# Scheme.net
KiCad netlist of a schematic drawn in Altium Designer
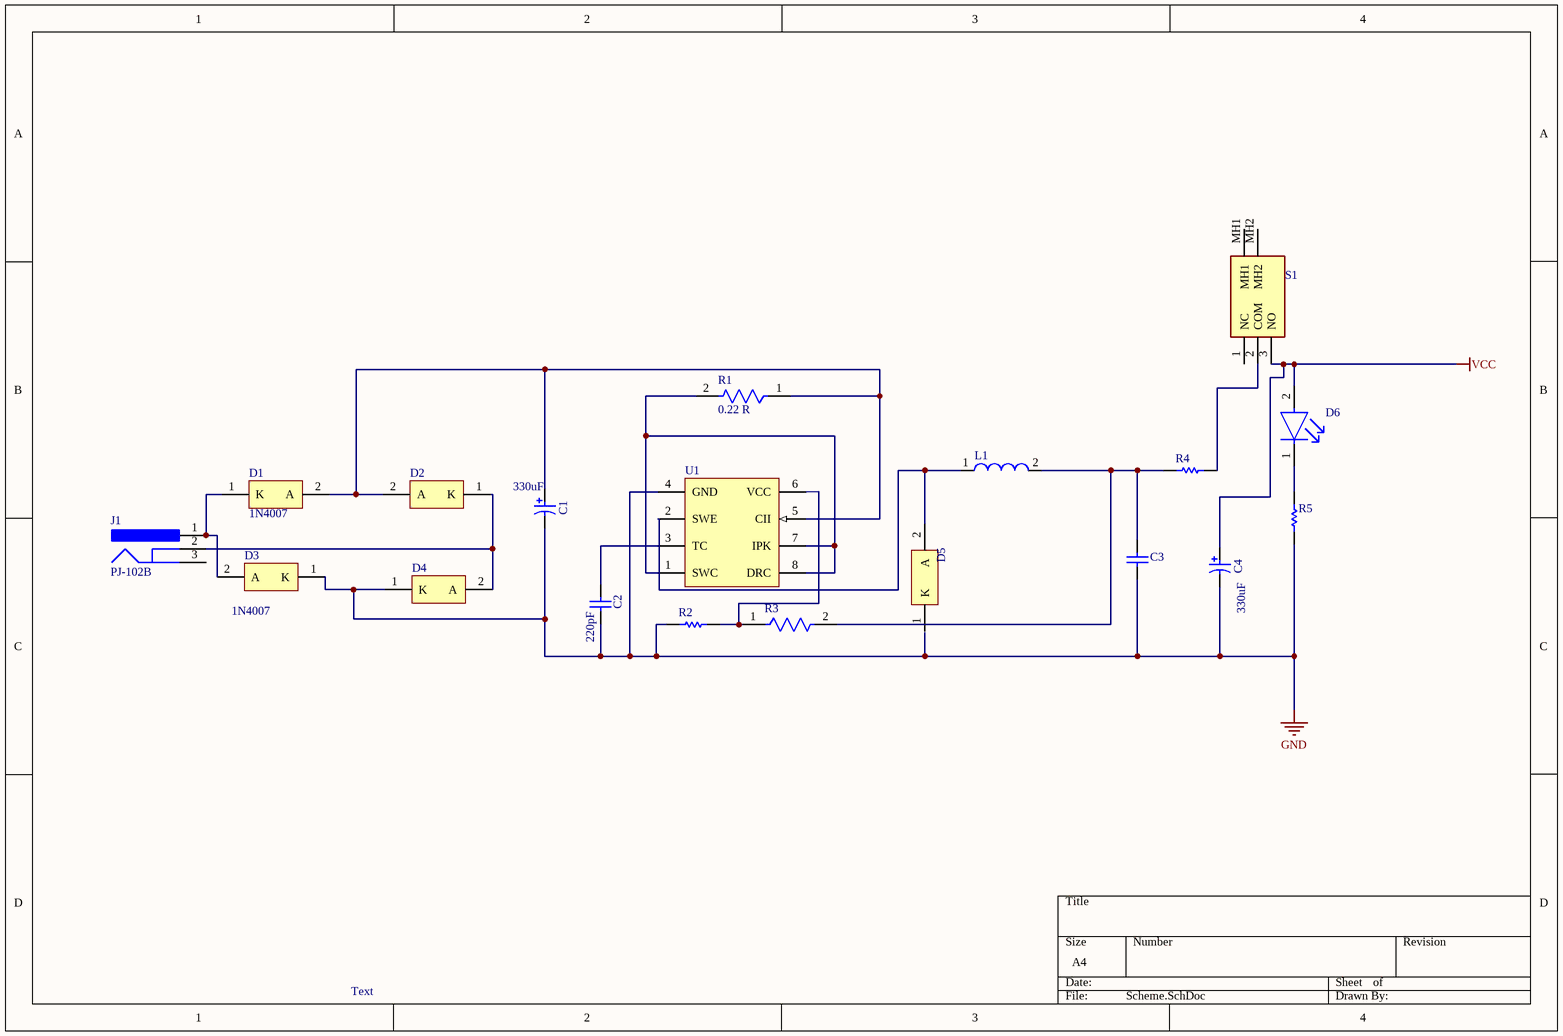
[diagram p0: Scheme.SchDoc]

(export (version "E")
  (design (tool "Eeschema 10.0.6"))
  (components
    (comp (ref "C1")
      (value "EEE-FK1V331P")
      (footprint "PNSC-EEE-FK1V331P_L")
      (description "Aluminum Electrolytic Capacitor, 330 uF, 35 V, -55 to 105 degC, 2-Pin CAPAE, RoHS, Tape and Reel")
      (fields (field (name "MANUFACTURER") "Panasonic"))
      (libsource (lib "Altium Content Vault") (part "CAP-P-2"))
    )
    (comp (ref "C2")
      (value "VJ0603D201KXAAJ")
      (footprint "CAPC1608X92X38LL15T08")
      (fields (field (name "MANUFACTURER") "Vitramon"))
      (libsource (lib "Altium Content Vault") (part "CAP"))
    )
    (comp (ref "C3")
      (value "GRM188R60J106ME47D")
      (footprint "CAPC1608X90X35NL10T15")
      (fields (field (name "MANUFACTURER") "Murata"))
      (libsource (lib "Altium Content Vault") (part "CAP"))
    )
    (comp (ref "C4")
      (value "EEE-FK1V331P")
      (footprint "PNSC-EEE-FK1V331P_L")
      (description "Aluminum Electrolytic Capacitor, 330 uF, 35 V, -55 to 105 degC, 2-Pin CAPAE, RoHS, Tape and Reel")
      (fields (field (name "MANUFACTURER") "Panasonic"))
      (libsource (lib "Altium Content Vault") (part "CAP-P-2"))
    )
    (comp (ref "D1")
      (value "1N4007")
      (footprint "ONSC-AXIAL_LEAD-2-59-10_P")
      (description "Standard Recovery Rectifier, 2-Pin Axial_Lead, Pb-Free, Bulk Bag")
      (fields (field (name "MANUFACTURER") "On Semiconductor"))
      (libsource (lib "") (part "ONSC-D-K1A2-2_A_1"))
    )
    (comp (ref "D2")
      (value "1N4007")
      (footprint "ONSC-AXIAL_LEAD-2-59-10_P")
      (description "Standard Recovery Rectifier, 2-Pin Axial_Lead, Pb-Free, Bulk Bag")
      (fields (field (name "MANUFACTURER") "On Semiconductor"))
      (libsource (lib "") (part "ONSC-D-K1A2-2_A_2"))
    )
    (comp (ref "D3")
      (value "1N4007")
      (footprint "ONSC-AXIAL_LEAD-2-59-10_P")
      (description "Standard Recovery Rectifier, 2-Pin Axial_Lead, Pb-Free, Bulk Bag")
      (fields (field (name "MANUFACTURER") "On Semiconductor"))
      (libsource (lib "") (part "ONSC-D-K1A2-2_A_2"))
    )
    (comp (ref "D4")
      (value "1N4007")
      (footprint "ONSC-AXIAL_LEAD-2-59-10_P")
      (description "Standard Recovery Rectifier, 2-Pin Axial_Lead, Pb-Free, Bulk Bag")
      (fields (field (name "MANUFACTURER") "On Semiconductor"))
      (libsource (lib "") (part "ONSC-D-K1A2-2_A_1"))
    )
    (comp (ref "D5")
      (value "MBRS140T3G")
      (footprint "ONSC-SMB-2-403A-03_H_V")
      (description "Schottky Power Rectifier, 2-Pin SMB, Pb-Free, Tape and Reel")
      (fields (field (name "MANUFACTURER") "On Semiconductor"))
      (libsource (lib "Altium Content Vault") (part "ONSC-D-K1A2-2_A"))
    )
    (comp (ref "D6")
      (value "LTST-C190GKT")
      (footprint "FP-LTST-C190GKT-MFG")
      (description "LED GREEN CLEAR CHIP SMD")
      (fields (field (name "VOLTAGE") "2V"))
      (libsource (lib "Altium Content Vault") (part "8706943c75ba83719d021d2fdc84c58"))
    )
    (comp (ref "J1")
      (value "PJ-102B")
      (footprint "CUI-PJ-102B_V")
      (fields (field (name "MANUFACTURER") "CUIInc."))
      (libsource (lib "Altium Content Vault") (part "JACK-2CD3-RN"))
    )
    (comp (ref "L1")
      (value "744774222")
      (footprint "WE-PD2-M")
      (description "SMD Power Inductor WE-PD2, L = 220 µH")
      (libsource (lib "Altium Content Vault") (part "PAS-IND-INDUCTOR-2"))
    )
    (comp (ref "R1")
      (value "CRCW04022K70FKED")
      (footprint "FP-CRCW0402-e3-IPC_C")
      (description "RES Thick Film, 0.22 Ω, 1%, 0.063W, 100ppm/°C, 0402")
      (fields (field (name "TOLERANCE") "1%") (field (name "RESISTANCE") "0.22 R"))
      (libsource (lib "Altium Content Vault") (part "1029c3af85768c4190bb7ad29bc67b5"))
    )
    (comp (ref "R2")
      (value "CRCW08051K00FKEA")
      (footprint "RESC2013X50X30NL20T20")
      (fields (field (name "MANUFACTURER") "Vishay Dale"))
      (libsource (lib "Altium Content Vault") (part "RES"))
    )
    (comp (ref "R3")
      (value "CRCW06033K00FKEA")
      (footprint "FP-CRCW0603-e3-MFG")
      (description "RES Thick Film, 3kΩ, 1%, 0.1W, 100ppm/°C, 0603")
      (fields (field (name "TOLERANCE") "1%"))
      (libsource (lib "Altium Content Vault") (part "1029c3af85768c4190bb7ad29bc67b5"))
    )
    (comp (ref "R4")
      (value "Jumper 2512(6432)")
      (footprint "RESC2512(6432)_L")
      (description "Jumper 2512 (6432 Metric)")
      (fields (field (name "TOLERANCE") "None"))
      (libsource (lib "Altium Content Vault") (part "RES"))
    )
    (comp (ref "R5")
      (value "RC0402FR-072K2L")
      (footprint "RESC1005X40X25NL05T10")
      (fields (field (name "MANUFACTURER") "Yageo / Phycomp"))
      (libsource (lib "Altium Content Vault") (part "RES"))
    )
    (comp (ref "S1")
      (value "MS12ASW40")
      (footprint "SamacSys:MS12ASW40")
      (description "Switch")
      (fields (field (name "MOUSER PART NUMBER") "633-MS12ASW40"))
      (libsource (lib "SamacSys") (part "MS12ASW40"))
    )
    (comp (ref "U1")
      (value "MC34063ACD-TR")
      (footprint "SO8_M")
      (description "DC/DC converter control circuit, 8-Pin SO, Tape and Reel")
      (libsource (lib "Altium Content Vault") (part "PM-SWREG-MC34063-IL8"))
    )
  )
  (nets
    (net (code "1") (name "GND") (class "Default")
      (node (ref "C1") (pin "2") (pinfunction "2_2") (pintype "passive"))
      (node (ref "C2") (pin "1") (pinfunction "1_1") (pintype "passive"))
      (node (ref "C3") (pin "1") (pinfunction "1_1") (pintype "passive"))
      (node (ref "C4") (pin "2") (pinfunction "2_2") (pintype "passive"))
      (node (ref "D3") (pin "1") (pinfunction "K_1") (pintype "passive"))
      (node (ref "D4") (pin "1") (pinfunction "K_1") (pintype "passive"))
      (node (ref "R2") (pin "1") (pinfunction "1_1") (pintype "passive"))
      (node (ref "R5") (pin "2") (pinfunction "2_2") (pintype "passive"))
      (node (ref "U1") (pin "4") (pinfunction "GND_4") (pintype "power_in"))
    )
    (net (code "2") (name "Net-(C3-Pad2)") (class "Default")
      (node (ref "C3") (pin "2") (pinfunction "2_2") (pintype "passive"))
      (node (ref "L1") (pin "2") (pinfunction "2_2") (pintype "passive"))
      (node (ref "R3") (pin "2") (pinfunction "2_2") (pintype "passive"))
      (node (ref "R4") (pin "1") (pinfunction "1_1") (pintype "passive"))
    )
    (net (code "3") (name "Net-(D1-A)") (class "Default")
      (node (ref "C1") (pin "1") (pinfunction "1_1") (pintype "passive"))
      (node (ref "D1") (pin "2") (pinfunction "A_2") (pintype "passive"))
      (node (ref "D2") (pin "2") (pinfunction "A_2") (pintype "passive"))
      (node (ref "R1") (pin "1") (pinfunction "1_1") (pintype "passive"))
      (node (ref "U1") (pin "5") (pinfunction "CII_5") (pintype "input"))
    )
    (net (code "4") (name "Net-(D1-K)") (class "Default")
      (node (ref "D1") (pin "1") (pinfunction "K_1") (pintype "passive"))
      (node (ref "D3") (pin "2") (pinfunction "A_2") (pintype "passive"))
      (node (ref "J1") (pin "1") (pinfunction "1_1") (pintype "passive"))
    )
    (net (code "5") (name "Net-(D2-K)") (class "Default")
      (node (ref "D2") (pin "1") (pinfunction "K_1") (pintype "passive"))
      (node (ref "D4") (pin "2") (pinfunction "A_2") (pintype "passive"))
      (node (ref "J1") (pin "2") (pinfunction "2_2") (pintype "passive"))
    )
    (net (code "6") (name "Net-(D5-A)") (class "Default")
      (node (ref "D5") (pin "2") (pinfunction "A_2") (pintype "passive"))
      (node (ref "L1") (pin "1") (pinfunction "1_1") (pintype "passive"))
      (node (ref "U1") (pin "2") (pinfunction "SWE_2") (pintype "open_emitter"))
    )
    (net (code "7") (name "Net-(D6-C)") (class "Default")
      (node (ref "D6") (pin "1") (pinfunction "C_1") (pintype "passive"))
      (node (ref "R5") (pin "1") (pinfunction "1_1") (pintype "passive"))
    )
    (net (code "8") (name "Net-(S1-COM)") (class "Default")
      (node (ref "R4") (pin "2") (pinfunction "2_2") (pintype "passive"))
      (node (ref "S1") (pin "2") (pinfunction "COM_2") (pintype "passive"))
    )
    (net (code "9") (name "Net-(U1-DRC)") (class "Default")
      (node (ref "R1") (pin "2") (pinfunction "2_2") (pintype "passive"))
      (node (ref "U1") (pin "1") (pinfunction "SWC_1") (pintype "open_collector"))
      (node (ref "U1") (pin "7") (pinfunction "IPK_7") (pintype "passive"))
      (node (ref "U1") (pin "8") (pinfunction "DRC_8") (pintype "open_collector"))
    )
    (net (code "10") (name "Net-(U1-TC)") (class "Default")
      (node (ref "C2") (pin "2") (pinfunction "2_2") (pintype "passive"))
      (node (ref "U1") (pin "3") (pinfunction "TC_3") (pintype "passive"))
    )
    (net (code "11") (name "Net-(U1-VCC)") (class "Default")
      (node (ref "R2") (pin "2") (pinfunction "2_2") (pintype "passive"))
      (node (ref "R3") (pin "1") (pinfunction "1_1") (pintype "passive"))
      (node (ref "U1") (pin "6") (pinfunction "VCC_6") (pintype "power_in"))
    )
    (net (code "12") (name "VCC") (class "Default")
      (node (ref "C4") (pin "1") (pinfunction "1_1") (pintype "passive"))
      (node (ref "D6") (pin "2") (pinfunction "A_2") (pintype "passive"))
      (node (ref "S1") (pin "3") (pinfunction "NO_3") (pintype "passive"))
    )
    (net (code "13") (name "unconnected-(D5-K-Pad1)") (class "Default")
      (node (ref "D5") (pin "1") (pinfunction "K_1") (pintype "passive"))
    )
    (net (code "14") (name "unconnected-(J1-Pad3)") (class "Default")
      (node (ref "J1") (pin "3") (pinfunction "3_3") (pintype "passive"))
    )
    (net (code "15") (name "unconnected-(S1-NC-Pad1)") (class "Default")
      (node (ref "S1") (pin "1") (pinfunction "NC_1") (pintype "passive"))
    )
    (net (code "16") (name "unconnected-(S1-PadMH1)") (class "Default")
      (node (ref "S1") (pin "MH1") (pinfunction "MH1_MH1") (pintype "passive"))
    )
    (net (code "17") (name "unconnected-(S1-PadMH2)") (class "Default")
      (node (ref "S1") (pin "MH2") (pinfunction "MH2_MH2") (pintype "passive"))
    )
  )
)
